# UVBoxSchematic.net
KiCad netlist of a schematic drawn in EAGLE
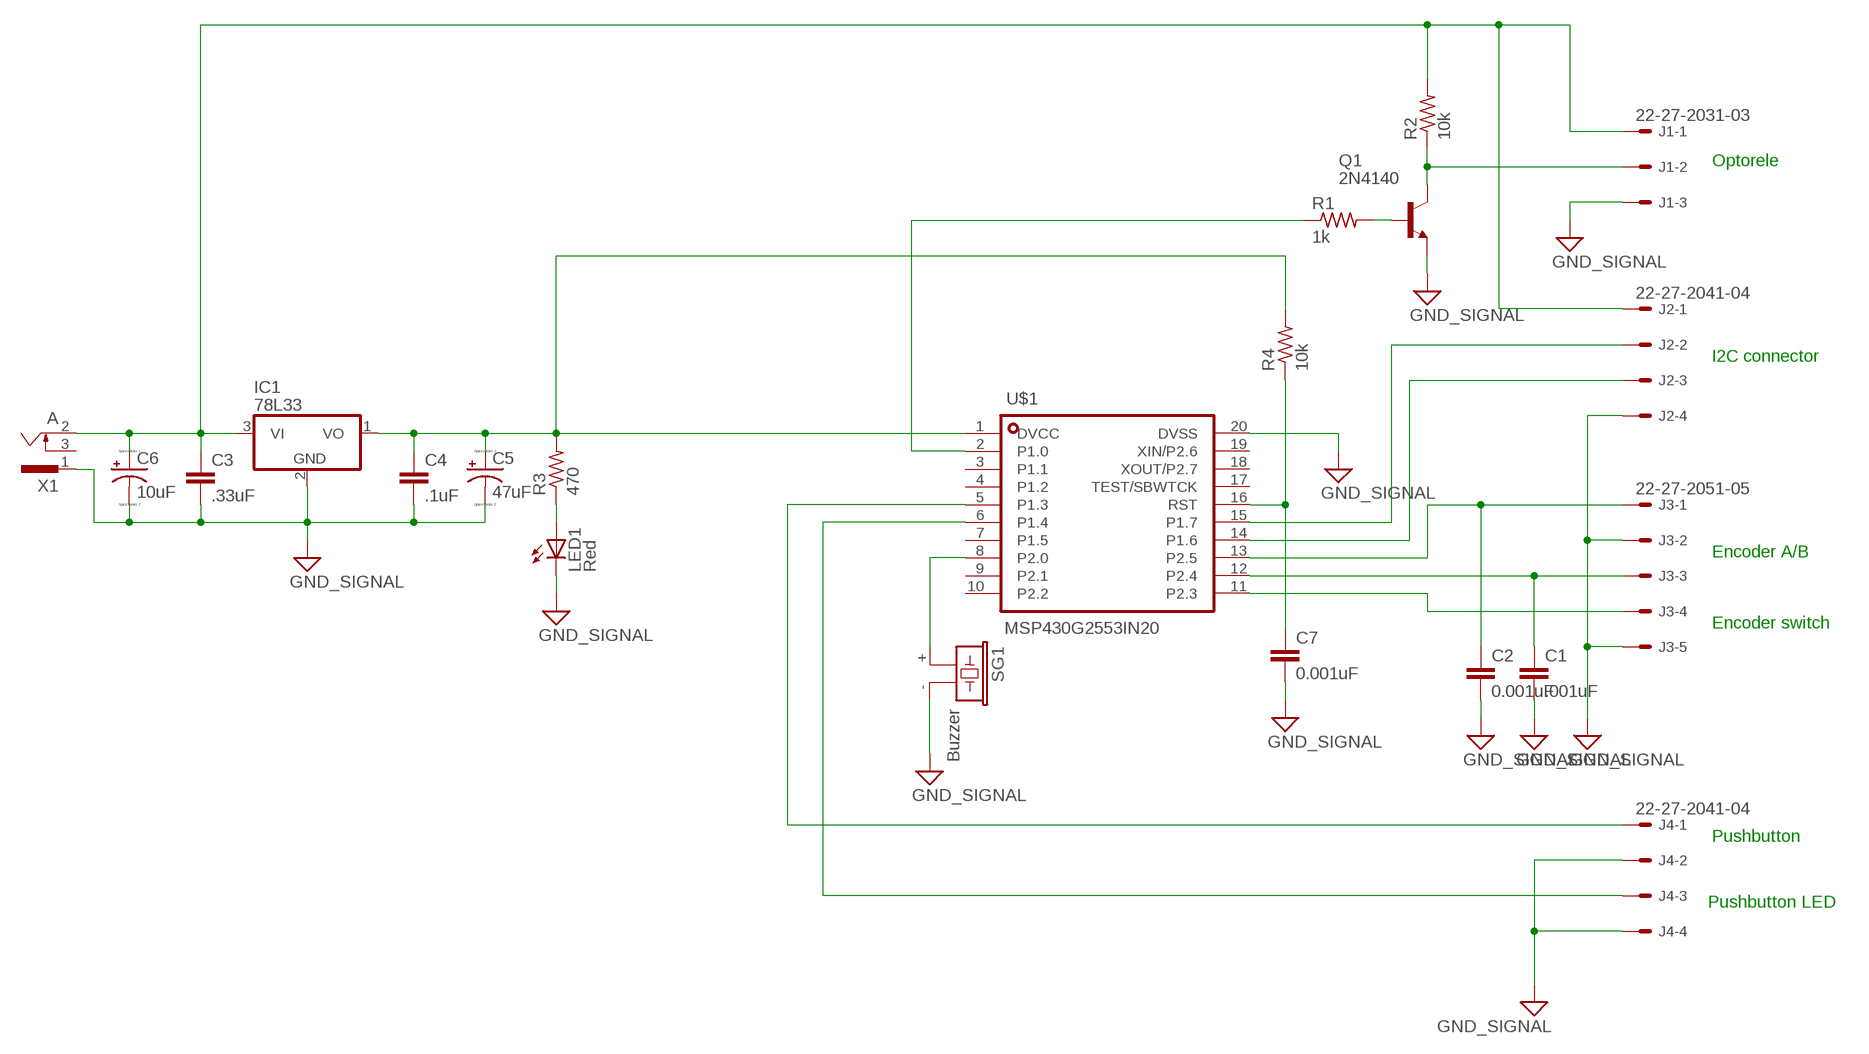
[diagram p0: schematic, sheet 1]

(export (version "E")
  (design (tool "Eeschema 10.0.6"))
  (components
    (comp (ref "C1")
      (value ".001uF")
      (footprint "eagle-import:C5B3")
      (libsource (lib "eagle-import") (part "C5/3"))
    )
    (comp (ref "C2")
      (value "0.001uF")
      (footprint "eagle-import:C5B3")
      (libsource (lib "eagle-import") (part "C5/3"))
    )
    (comp (ref "C3")
      (value ".33uF")
      (footprint "eagle-import:C5B3")
      (libsource (lib "eagle-import") (part "C5/3"))
    )
    (comp (ref "C4")
      (value ".1uF")
      (footprint "eagle-import:C5B3")
      (libsource (lib "eagle-import") (part "C5/3"))
    )
    (comp (ref "C5")
      (value "47uF")
      (footprint "eagle-import:B45181A")
      (libsource (lib "eagle-import") (part "CPOL-USB45181A"))
    )
    (comp (ref "C6")
      (value "10uF")
      (footprint "eagle-import:B45181A")
      (libsource (lib "eagle-import") (part "CPOL-USB45181A"))
    )
    (comp (ref "C7")
      (value "0.001uF")
      (footprint "eagle-import:C5B3")
      (libsource (lib "eagle-import") (part "C5/3"))
    )
    (comp (ref "IC1")
      (value "78L33")
      (footprint "eagle-import:TO92")
      (libsource (lib "eagle-import") (part "78ZL05"))
    )
    (comp (ref "J1")
      (value "22-27-2031-03")
      (footprint "eagle-import:6410-03")
      (libsource (lib "eagle-import") (part "22-?-0327-2031"))
    )
    (comp (ref "J2")
      (value "22-27-2041-04")
      (footprint "eagle-import:6410-04")
      (libsource (lib "eagle-import") (part "22-?-0427-2041"))
    )
    (comp (ref "J3")
      (value "22-27-2051-05")
      (footprint "eagle-import:6410-05")
      (libsource (lib "eagle-import") (part "22-?-0527-2051"))
    )
    (comp (ref "J4")
      (value "22-27-2041-04")
      (footprint "eagle-import:6410-04")
      (libsource (lib "eagle-import") (part "22-?-0427-2041"))
    )
    (comp (ref "LED1")
      (value "Red")
      (footprint "eagle-import:LED3MM")
      (libsource (lib "eagle-import") (part "LED3MM"))
    )
    (comp (ref "Q1")
      (value "2N4140")
      (footprint "eagle-import:TO18")
      (libsource (lib "eagle-import") (part "2N4104"))
    )
    (comp (ref "R1")
      (value "1k")
      (footprint "eagle-import:0204_7")
      (libsource (lib "eagle-import") (part "R-US_0204/7"))
    )
    (comp (ref "R2")
      (value "10k")
      (footprint "eagle-import:0204_7")
      (libsource (lib "eagle-import") (part "R-US_0204/7"))
    )
    (comp (ref "R3")
      (value "470")
      (footprint "eagle-import:0204_7")
      (libsource (lib "eagle-import") (part "R-US_0204/7"))
    )
    (comp (ref "R4")
      (value "10k")
      (footprint "eagle-import:0204_7")
      (libsource (lib "eagle-import") (part "R-US_0204/7"))
    )
    (comp (ref "SG1")
      (value "Buzzer")
      (footprint "eagle-import:F_CM04P")
      (libsource (lib "eagle-import") (part "F/CM04P"))
    )
    (comp (ref "U$1")
      (value "MSP430G2553IN20")
      (footprint "eagle-import:DIP20")
      (libsource (lib "eagle-import") (part "MSP430G2553IN20"))
    )
    (comp (ref "X1")
      (value "A")
      (footprint "eagle-import:SCD-014-A")
      (libsource (lib "eagle-import") (part "SCD-014A"))
    )
  )
  (nets
    (net (code "1") (name "GND_SIGNAL") (class "Default")
      (node (ref "C1") (pin "2") (pinfunction "2_2") (pintype "passive"))
      (node (ref "C2") (pin "2") (pinfunction "2_2") (pintype "passive"))
      (node (ref "C3") (pin "2") (pinfunction "2_2") (pintype "passive"))
      (node (ref "C4") (pin "2") (pinfunction "2_2") (pintype "passive"))
      (node (ref "C5") (pin "-") (pinfunction "-_-") (pintype "passive"))
      (node (ref "C6") (pin "-") (pinfunction "-_-") (pintype "passive"))
      (node (ref "C7") (pin "2") (pinfunction "2_2") (pintype "passive"))
      (node (ref "IC1") (pin "2") (pinfunction "GND_2") (pintype "passive"))
      (node (ref "J1") (pin "3") (pinfunction "S_3") (pintype "passive"))
      (node (ref "J2") (pin "4") (pinfunction "S_4") (pintype "passive"))
      (node (ref "J3") (pin "2") (pinfunction "S_2") (pintype "passive"))
      (node (ref "J3") (pin "5") (pinfunction "S_5") (pintype "passive"))
      (node (ref "J4") (pin "2") (pinfunction "S_2") (pintype "passive"))
      (node (ref "J4") (pin "4") (pinfunction "S_4") (pintype "passive"))
      (node (ref "LED1") (pin "K") (pinfunction "C_K") (pintype "passive"))
      (node (ref "Q1") (pin "1") (pinfunction "E_1") (pintype "passive"))
      (node (ref "SG1") (pin "-") (pinfunction "2_-") (pintype "passive"))
      (node (ref "U$1") (pin "20") (pinfunction "DVSS_20") (pintype "power_in"))
      (node (ref "X1") (pin "1") (pinfunction "1_1") (pintype "passive"))
    )
    (net (code "2") (name "Net-(IC1-VI)") (class "Default")
      (node (ref "C3") (pin "1") (pinfunction "1_1") (pintype "passive"))
      (node (ref "C6") (pin "+") (pinfunction "+_+") (pintype "passive"))
      (node (ref "IC1") (pin "3") (pinfunction "VI_3") (pintype "input"))
      (node (ref "J1") (pin "1") (pinfunction "S_1") (pintype "passive"))
      (node (ref "J2") (pin "1") (pinfunction "S_1") (pintype "passive"))
      (node (ref "R2") (pin "2") (pinfunction "2_2") (pintype "passive"))
      (node (ref "X1") (pin "2") (pinfunction "2_2") (pintype "passive"))
    )
    (net (code "3") (name "Net-(IC1-VO)") (class "Default")
      (node (ref "C4") (pin "1") (pinfunction "1_1") (pintype "passive"))
      (node (ref "C5") (pin "+") (pinfunction "+_+") (pintype "passive"))
      (node (ref "IC1") (pin "1") (pinfunction "VO_1") (pintype "passive"))
      (node (ref "R3") (pin "2") (pinfunction "2_2") (pintype "passive"))
      (node (ref "R4") (pin "2") (pinfunction "2_2") (pintype "passive"))
      (node (ref "U$1") (pin "1") (pinfunction "DVCC_1") (pintype "power_in"))
    )
    (net (code "4") (name "Net-(J1B-S)") (class "Default")
      (node (ref "J1") (pin "2") (pinfunction "S_2") (pintype "passive"))
      (node (ref "Q1") (pin "3") (pinfunction "C_3") (pintype "passive"))
      (node (ref "R2") (pin "1") (pinfunction "1_1") (pintype "passive"))
    )
    (net (code "5") (name "Net-(J2B-S)") (class "Default")
      (node (ref "J2") (pin "2") (pinfunction "S_2") (pintype "passive"))
      (node (ref "U$1") (pin "15") (pinfunction "P1.7_15") (pintype "bidirectional"))
    )
    (net (code "6") (name "Net-(J2C-S)") (class "Default")
      (node (ref "J2") (pin "3") (pinfunction "S_3") (pintype "passive"))
      (node (ref "U$1") (pin "14") (pinfunction "P1.6_14") (pintype "bidirectional"))
    )
    (net (code "7") (name "Net-(J3A-S)") (class "Default")
      (node (ref "C2") (pin "1") (pinfunction "1_1") (pintype "passive"))
      (node (ref "J3") (pin "1") (pinfunction "S_1") (pintype "passive"))
      (node (ref "U$1") (pin "13") (pinfunction "P2.5_13") (pintype "bidirectional"))
    )
    (net (code "8") (name "Net-(J3C-S)") (class "Default")
      (node (ref "C1") (pin "1") (pinfunction "1_1") (pintype "passive"))
      (node (ref "J3") (pin "3") (pinfunction "S_3") (pintype "passive"))
      (node (ref "U$1") (pin "12") (pinfunction "P2.4_12") (pintype "bidirectional"))
    )
    (net (code "9") (name "Net-(J3D-S)") (class "Default")
      (node (ref "J3") (pin "4") (pinfunction "S_4") (pintype "passive"))
      (node (ref "U$1") (pin "11") (pinfunction "P2.3_11") (pintype "bidirectional"))
    )
    (net (code "10") (name "Net-(J4A-S)") (class "Default")
      (node (ref "J4") (pin "1") (pinfunction "S_1") (pintype "passive"))
      (node (ref "U$1") (pin "5") (pinfunction "P1.3_5") (pintype "bidirectional"))
    )
    (net (code "11") (name "Net-(J4C-S)") (class "Default")
      (node (ref "J4") (pin "3") (pinfunction "S_3") (pintype "passive"))
      (node (ref "U$1") (pin "6") (pinfunction "P1.4_6") (pintype "bidirectional"))
    )
    (net (code "12") (name "Net-(LED1-PadA)") (class "Default")
      (node (ref "LED1") (pin "A") (pinfunction "A_A") (pintype "passive"))
      (node (ref "R3") (pin "1") (pinfunction "1_1") (pintype "passive"))
    )
    (net (code "13") (name "Net-(Q1-B)") (class "Default")
      (node (ref "Q1") (pin "2") (pinfunction "B_2") (pintype "passive"))
      (node (ref "R1") (pin "2") (pinfunction "2_2") (pintype "passive"))
    )
    (net (code "14") (name "Net-(SG1-1)") (class "Default")
      (node (ref "SG1") (pin "+") (pinfunction "1_+") (pintype "passive"))
      (node (ref "U$1") (pin "8") (pinfunction "P2.0_8") (pintype "bidirectional"))
    )
    (net (code "15") (name "Net-(U$1-P1.0)") (class "Default")
      (node (ref "R1") (pin "1") (pinfunction "1_1") (pintype "passive"))
      (node (ref "U$1") (pin "2") (pinfunction "P1.0_2") (pintype "bidirectional"))
    )
    (net (code "16") (name "Net-(U$1-RST)") (class "Default")
      (node (ref "C7") (pin "1") (pinfunction "1_1") (pintype "passive"))
      (node (ref "R4") (pin "1") (pinfunction "1_1") (pintype "passive"))
      (node (ref "U$1") (pin "16") (pinfunction "RST_16") (pintype "bidirectional"))
    )
    (net (code "17") (name "unconnected-(U$1-P1.1-Pad3)") (class "Default")
      (node (ref "U$1") (pin "3") (pinfunction "P1.1_3") (pintype "bidirectional"))
    )
    (net (code "18") (name "unconnected-(U$1-P1.2-Pad4)") (class "Default")
      (node (ref "U$1") (pin "4") (pinfunction "P1.2_4") (pintype "bidirectional"))
    )
    (net (code "19") (name "unconnected-(U$1-P1.5-Pad7)") (class "Default")
      (node (ref "U$1") (pin "7") (pinfunction "P1.5_7") (pintype "bidirectional"))
    )
    (net (code "20") (name "unconnected-(U$1-P2.1-Pad9)") (class "Default")
      (node (ref "U$1") (pin "9") (pinfunction "P2.1_9") (pintype "bidirectional"))
    )
    (net (code "21") (name "unconnected-(U$1-P2.2-Pad10)") (class "Default")
      (node (ref "U$1") (pin "10") (pinfunction "P2.2_10") (pintype "bidirectional"))
    )
    (net (code "22") (name "unconnected-(U$1-TEST{slash}SBWTCK-Pad17)") (class "Default")
      (node (ref "U$1") (pin "17") (pinfunction "TEST/SBWTCK_17") (pintype "bidirectional"))
    )
    (net (code "23") (name "unconnected-(U$1-XIN{slash}P2.6-Pad19)") (class "Default")
      (node (ref "U$1") (pin "19") (pinfunction "XIN/P2.6_19") (pintype "bidirectional"))
    )
    (net (code "24") (name "unconnected-(U$1-XOUT{slash}P2.7-Pad18)") (class "Default")
      (node (ref "U$1") (pin "18") (pinfunction "XOUT/P2.7_18") (pintype "bidirectional"))
    )
    (net (code "25") (name "unconnected-(X1-Pad3)") (class "Default")
      (node (ref "X1") (pin "3") (pinfunction "3_3") (pintype "passive"))
    )
  )
)
